# RJ45_Connector_and_ESD_Diodes.net
KiCad netlist of a schematic drawn in Altium Designer
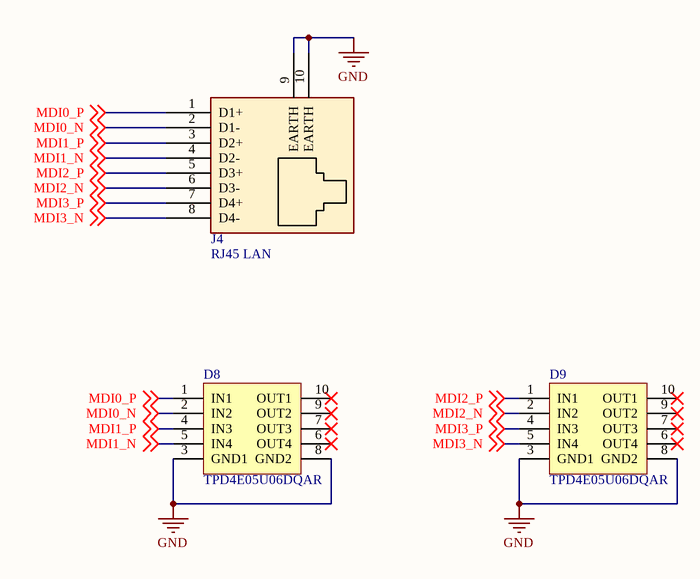
[diagram p0: RJ45 Connector and ESD Diodes.SchDoc]

(export (version "E")
  (design (tool "Eeschema 10.0.6"))
  (components
    (comp (ref "D8")
      (value "TPD4E05U06DQAR")
      (footprint "DIO_USON-10_SMD")
      (description "14V Clamp 2.5A (8/20µs) Ipp Tvs Diode Surface Mount 10-USON (2.5x1)")
      (fields (field (name "MANUFACTURER") "Texas Instruments"))
      (libsource (lib "RK3399 _Module_Schlib") (part "DIO-T_5.5V-14V-2.5A-10-USON"))
    )
    (comp (ref "D9")
      (value "TPD4E05U06DQAR")
      (footprint "DIO_USON-10_SMD")
      (description "14V Clamp 2.5A (8/20µs) Ipp Tvs Diode Surface Mount 10-USON (2.5x1)")
      (fields (field (name "MANUFACTURER") "Texas Instruments"))
      (libsource (lib "RK3399 _Module_Schlib") (part "DIO-T_5.5V-14V-2.5A-10-USON"))
    )
    (comp (ref "J4")
      (value "RJ45 LAN")
      (footprint "CON10_P106_RJ45_TH_ST")
      (description "8 Pins, 2 Row 2.54mm Pitch, right angle Connector, male")
      (fields
        (field (name "MANUFACTURER") "Assmann")
        (field (name "MANUFACTURER PART NUMBER") "A-2004-2-4-LPS-N-R")
      )
      (libsource (lib "RK3399 _Module_Schlib") (part "CON-SKT-RJ_8C8P-RA-TH"))
    )
  )
  (nets
    (net (code "1") (name "GND") (class "Default")
      (node (ref "D8") (pin "3") (pinfunction "GND1_3") (pintype "passive"))
      (node (ref "D8") (pin "8") (pinfunction "GND2_8") (pintype "passive"))
      (node (ref "D9") (pin "3") (pinfunction "GND1_3") (pintype "passive"))
      (node (ref "D9") (pin "8") (pinfunction "GND2_8") (pintype "passive"))
      (node (ref "J4") (pin "10") (pinfunction "EARTH_10") (pintype "passive"))
      (node (ref "J4") (pin "9") (pinfunction "EARTH_9") (pintype "passive"))
    )
    (net (code "2") (name "MDI0_N") (class "Default")
      (node (ref "D8") (pin "2") (pinfunction "IN2_2") (pintype "passive"))
      (node (ref "J4") (pin "2") (pinfunction "D1-_2") (pintype "passive"))
    )
    (net (code "3") (name "MDI0_P") (class "Default")
      (node (ref "D8") (pin "1") (pinfunction "IN1_1") (pintype "passive"))
      (node (ref "J4") (pin "1") (pinfunction "D1+_1") (pintype "passive"))
    )
    (net (code "4") (name "MDI1_N") (class "Default")
      (node (ref "D8") (pin "5") (pinfunction "IN4_5") (pintype "passive"))
      (node (ref "J4") (pin "4") (pinfunction "D2-_4") (pintype "passive"))
    )
    (net (code "5") (name "MDI1_P") (class "Default")
      (node (ref "D8") (pin "4") (pinfunction "IN3_4") (pintype "passive"))
      (node (ref "J4") (pin "3") (pinfunction "D2+_3") (pintype "passive"))
    )
    (net (code "6") (name "MDI2_N") (class "Default")
      (node (ref "D9") (pin "2") (pinfunction "IN2_2") (pintype "passive"))
      (node (ref "J4") (pin "6") (pinfunction "D3-_6") (pintype "passive"))
    )
    (net (code "7") (name "MDI2_P") (class "Default")
      (node (ref "D9") (pin "1") (pinfunction "IN1_1") (pintype "passive"))
      (node (ref "J4") (pin "5") (pinfunction "D3+_5") (pintype "passive"))
    )
    (net (code "8") (name "MDI3_N") (class "Default")
      (node (ref "D9") (pin "5") (pinfunction "IN4_5") (pintype "passive"))
      (node (ref "J4") (pin "8") (pinfunction "D4-_8") (pintype "passive"))
    )
    (net (code "9") (name "MDI3_P") (class "Default")
      (node (ref "D9") (pin "4") (pinfunction "IN3_4") (pintype "passive"))
      (node (ref "J4") (pin "7") (pinfunction "D4+_7") (pintype "passive"))
    )
    (net (code "10") (name "unconnected-(D8-OUT1-Pad10)") (class "Default")
      (node (ref "D8") (pin "10") (pinfunction "OUT1_10") (pintype "passive+no_connect"))
    )
    (net (code "11") (name "unconnected-(D8-OUT2-Pad9)") (class "Default")
      (node (ref "D8") (pin "9") (pinfunction "OUT2_9") (pintype "passive+no_connect"))
    )
    (net (code "12") (name "unconnected-(D8-OUT3-Pad7)") (class "Default")
      (node (ref "D8") (pin "7") (pinfunction "OUT3_7") (pintype "passive+no_connect"))
    )
    (net (code "13") (name "unconnected-(D8-OUT4-Pad6)") (class "Default")
      (node (ref "D8") (pin "6") (pinfunction "OUT4_6") (pintype "passive+no_connect"))
    )
    (net (code "14") (name "unconnected-(D9-OUT1-Pad10)") (class "Default")
      (node (ref "D9") (pin "10") (pinfunction "OUT1_10") (pintype "passive+no_connect"))
    )
    (net (code "15") (name "unconnected-(D9-OUT2-Pad9)") (class "Default")
      (node (ref "D9") (pin "9") (pinfunction "OUT2_9") (pintype "passive+no_connect"))
    )
    (net (code "16") (name "unconnected-(D9-OUT3-Pad7)") (class "Default")
      (node (ref "D9") (pin "7") (pinfunction "OUT3_7") (pintype "passive+no_connect"))
    )
    (net (code "17") (name "unconnected-(D9-OUT4-Pad6)") (class "Default")
      (node (ref "D9") (pin "6") (pinfunction "OUT4_6") (pintype "passive+no_connect"))
    )
  )
)
